# Temp_board_v4_0.net
KiCad netlist of a schematic drawn in EAGLE
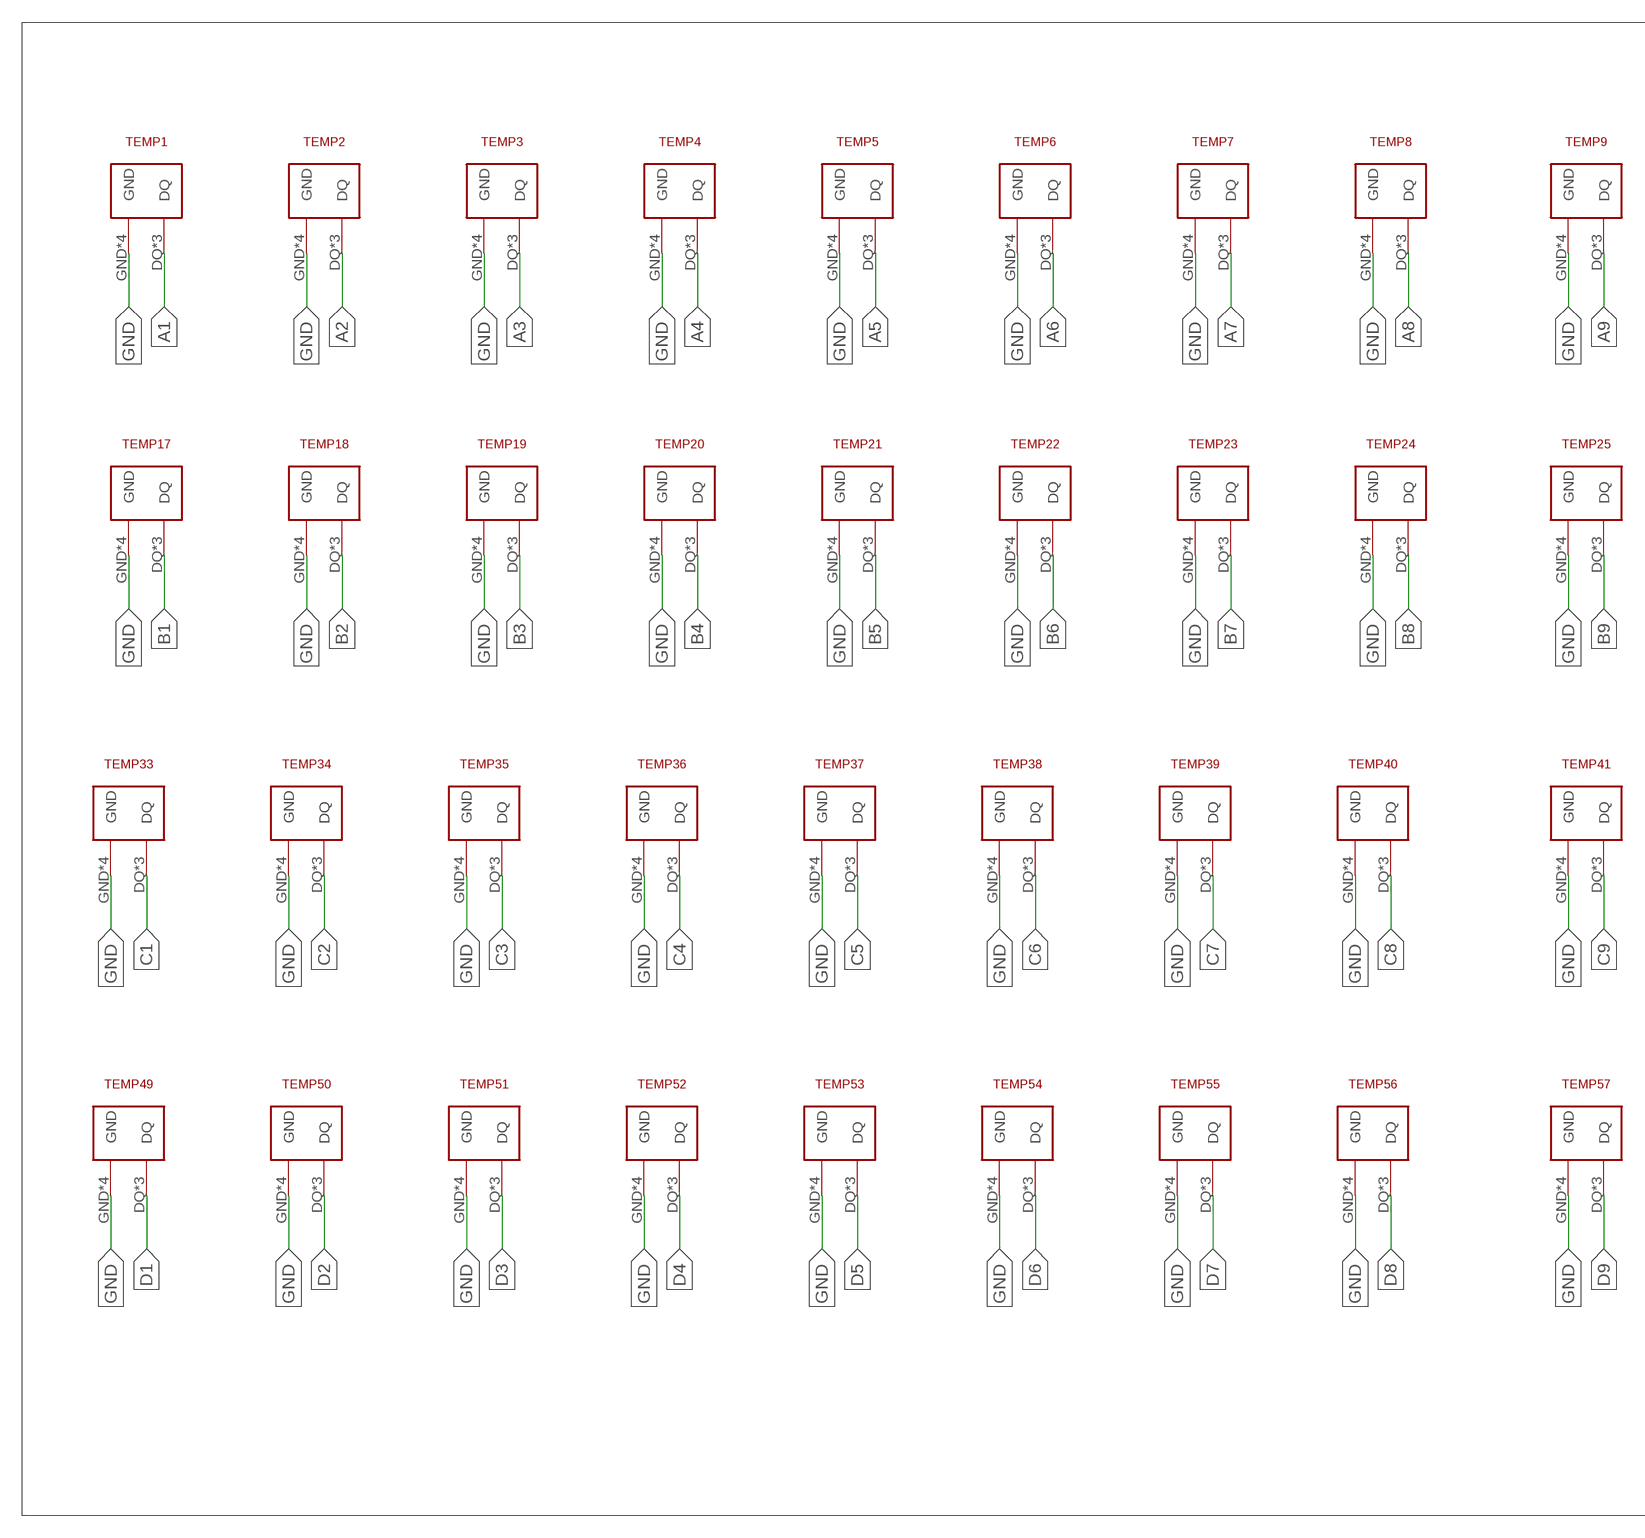
[diagram p0: schematic, sheet 1, part 1 of 2]
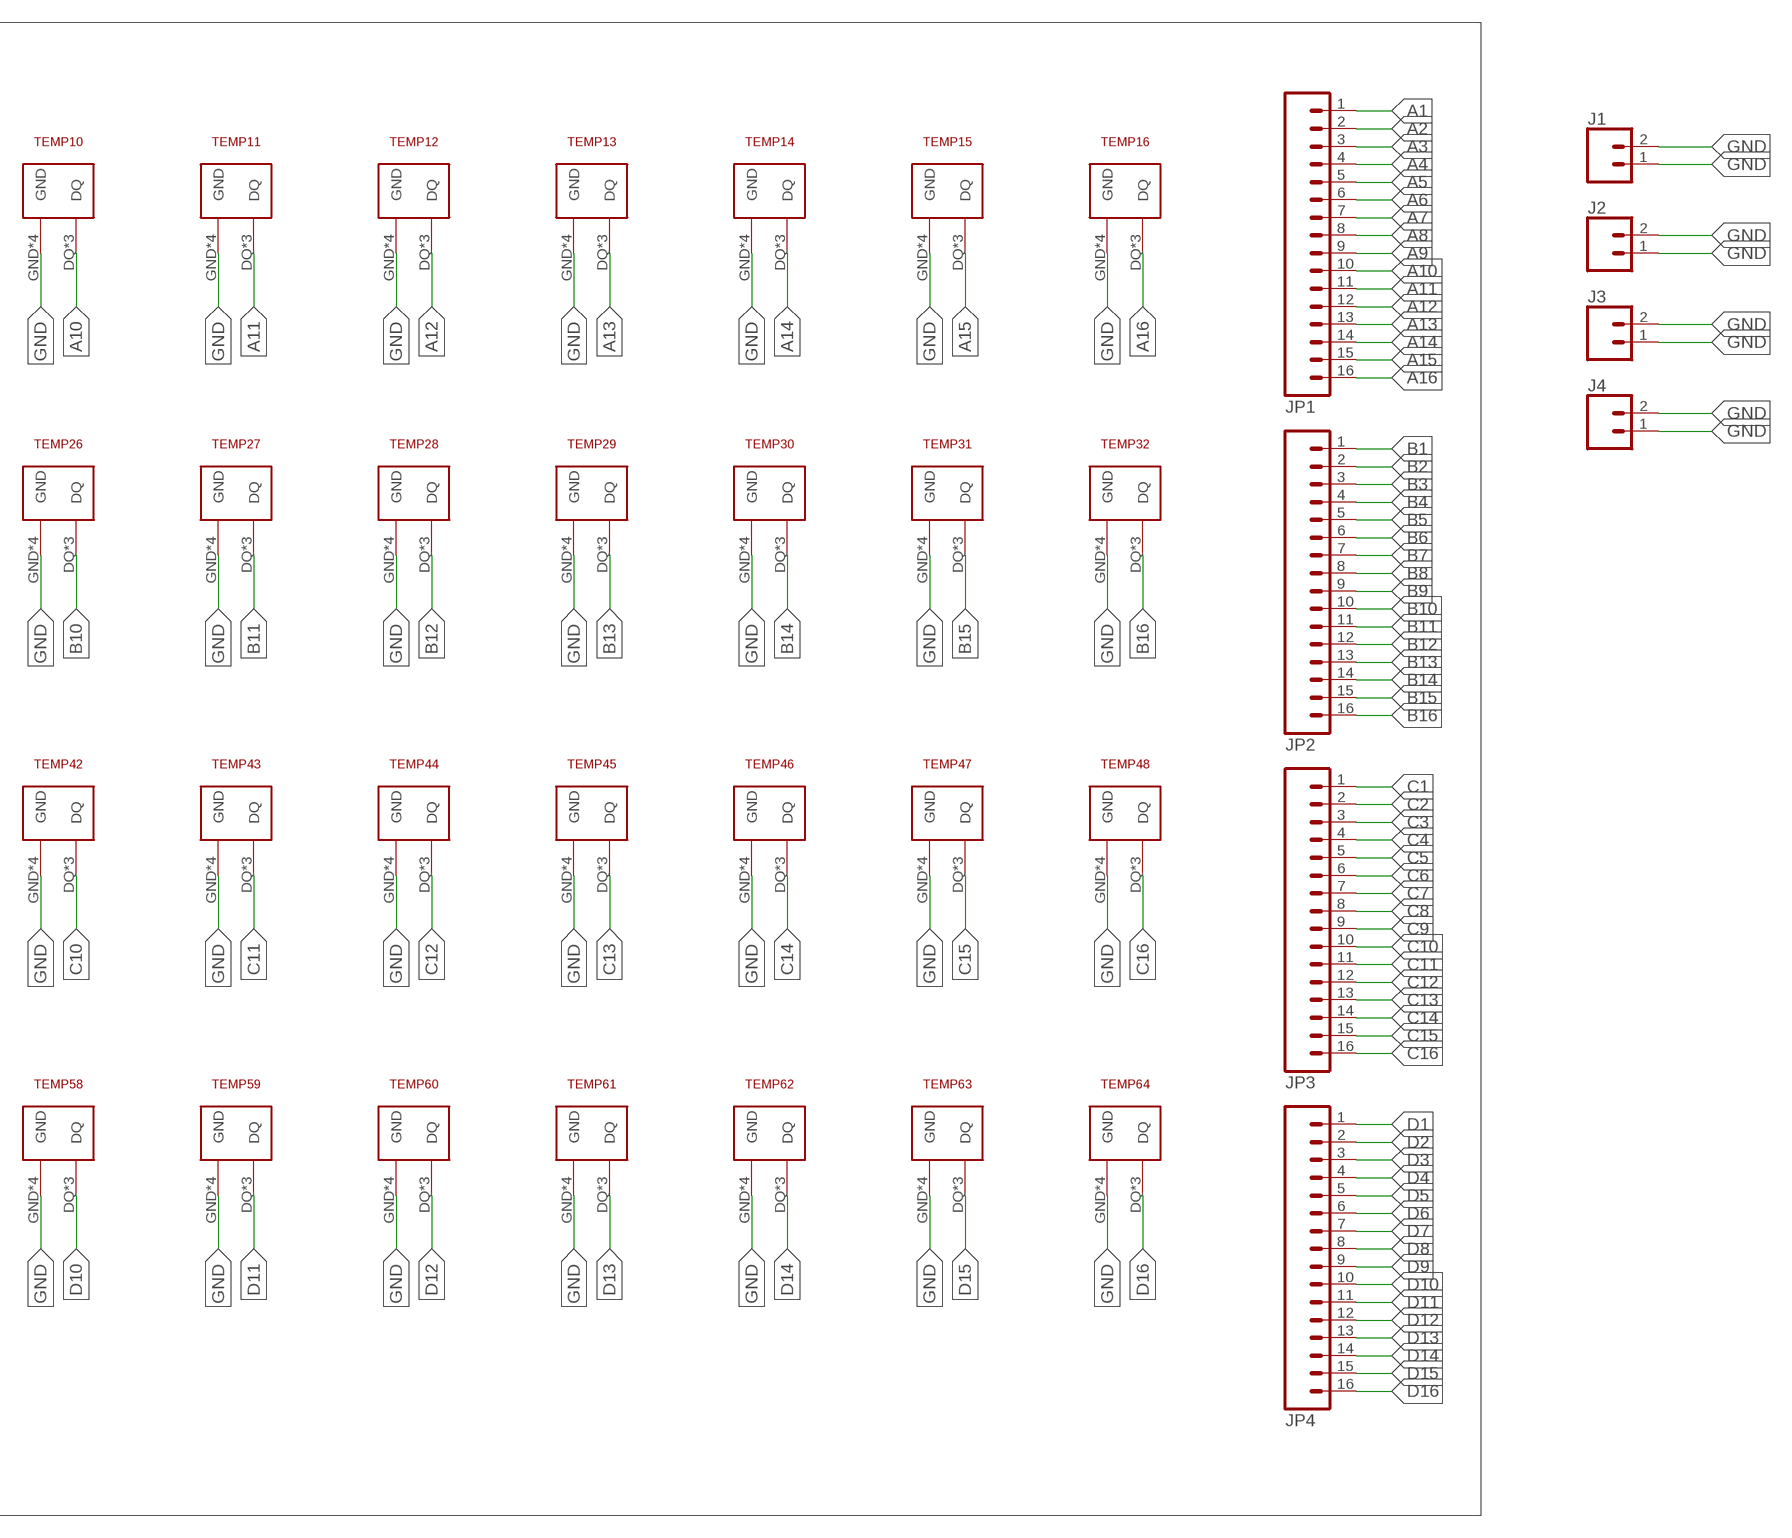
[diagram p1: schematic, sheet 1, part 2 of 2]

(export (version "E")
  (design (tool "Eeschema 10.0.6"))
  (components
    (comp (ref "J1")
      (value "CONN_02")
      (footprint "eagle-import:1X02")
      (libsource (lib "eagle-import") (part "CONN_02"))
    )
    (comp (ref "J2")
      (value "CONN_02")
      (footprint "eagle-import:1X02")
      (libsource (lib "eagle-import") (part "CONN_02"))
    )
    (comp (ref "J3")
      (value "CONN_02")
      (footprint "eagle-import:1X02")
      (libsource (lib "eagle-import") (part "CONN_02"))
    )
    (comp (ref "J4")
      (value "CONN_02")
      (footprint "eagle-import:1X02")
      (libsource (lib "eagle-import") (part "CONN_02"))
    )
    (comp (ref "JP1")
      (value "M16PTH")
      (footprint "eagle-import:1X16")
      (libsource (lib "eagle-import") (part "M16PTH"))
    )
    (comp (ref "JP2")
      (value "M16PTH")
      (footprint "eagle-import:1X16")
      (libsource (lib "eagle-import") (part "M16PTH"))
    )
    (comp (ref "JP3")
      (value "M16PTH")
      (footprint "eagle-import:1X16")
      (libsource (lib "eagle-import") (part "M16PTH"))
    )
    (comp (ref "JP4")
      (value "M16PTH")
      (footprint "eagle-import:1X16")
      (libsource (lib "eagle-import") (part "M16PTH"))
    )
    (comp (ref "TEMP1")
      (value "TEMP_TEST_ALL")
      (footprint "eagle-import:TEMP_TEST_PACKAGE")
      (libsource (lib "eagle-import") (part "TEMP_TEST_ALL"))
    )
    (comp (ref "TEMP2")
      (value "TEMP_TEST_ALL")
      (footprint "eagle-import:TEMP_TEST_PACKAGE")
      (libsource (lib "eagle-import") (part "TEMP_TEST_ALL"))
    )
    (comp (ref "TEMP3")
      (value "TEMP_TEST_ALL")
      (footprint "eagle-import:TEMP_TEST_PACKAGE")
      (libsource (lib "eagle-import") (part "TEMP_TEST_ALL"))
    )
    (comp (ref "TEMP4")
      (value "TEMP_TEST_ALL")
      (footprint "eagle-import:TEMP_TEST_PACKAGE")
      (libsource (lib "eagle-import") (part "TEMP_TEST_ALL"))
    )
    (comp (ref "TEMP5")
      (value "TEMP_TEST_ALL")
      (footprint "eagle-import:TEMP_TEST_PACKAGE")
      (libsource (lib "eagle-import") (part "TEMP_TEST_ALL"))
    )
    (comp (ref "TEMP6")
      (value "TEMP_TEST_ALL")
      (footprint "eagle-import:TEMP_TEST_PACKAGE")
      (libsource (lib "eagle-import") (part "TEMP_TEST_ALL"))
    )
    (comp (ref "TEMP7")
      (value "TEMP_TEST_ALL")
      (footprint "eagle-import:TEMP_TEST_PACKAGE")
      (libsource (lib "eagle-import") (part "TEMP_TEST_ALL"))
    )
    (comp (ref "TEMP8")
      (value "TEMP_TEST_ALL")
      (footprint "eagle-import:TEMP_TEST_PACKAGE")
      (libsource (lib "eagle-import") (part "TEMP_TEST_ALL"))
    )
    (comp (ref "TEMP9")
      (value "TEMP_TEST_ALL")
      (footprint "eagle-import:TEMP_TEST_PACKAGE")
      (libsource (lib "eagle-import") (part "TEMP_TEST_ALL"))
    )
    (comp (ref "TEMP10")
      (value "TEMP_TEST_ALL")
      (footprint "eagle-import:TEMP_TEST_PACKAGE")
      (libsource (lib "eagle-import") (part "TEMP_TEST_ALL"))
    )
    (comp (ref "TEMP11")
      (value "TEMP_TEST_ALL")
      (footprint "eagle-import:TEMP_TEST_PACKAGE")
      (libsource (lib "eagle-import") (part "TEMP_TEST_ALL"))
    )
    (comp (ref "TEMP12")
      (value "TEMP_TEST_ALL")
      (footprint "eagle-import:TEMP_TEST_PACKAGE")
      (libsource (lib "eagle-import") (part "TEMP_TEST_ALL"))
    )
    (comp (ref "TEMP13")
      (value "TEMP_TEST_ALL")
      (footprint "eagle-import:TEMP_TEST_PACKAGE")
      (libsource (lib "eagle-import") (part "TEMP_TEST_ALL"))
    )
    (comp (ref "TEMP14")
      (value "TEMP_TEST_ALL")
      (footprint "eagle-import:TEMP_TEST_PACKAGE")
      (libsource (lib "eagle-import") (part "TEMP_TEST_ALL"))
    )
    (comp (ref "TEMP15")
      (value "TEMP_TEST_ALL")
      (footprint "eagle-import:TEMP_TEST_PACKAGE")
      (libsource (lib "eagle-import") (part "TEMP_TEST_ALL"))
    )
    (comp (ref "TEMP16")
      (value "TEMP_TEST_ALL")
      (footprint "eagle-import:TEMP_TEST_PACKAGE")
      (libsource (lib "eagle-import") (part "TEMP_TEST_ALL"))
    )
    (comp (ref "TEMP17")
      (value "TEMP_TEST_ALL")
      (footprint "eagle-import:TEMP_TEST_PACKAGE")
      (libsource (lib "eagle-import") (part "TEMP_TEST_ALL"))
    )
    (comp (ref "TEMP18")
      (value "TEMP_TEST_ALL")
      (footprint "eagle-import:TEMP_TEST_PACKAGE")
      (libsource (lib "eagle-import") (part "TEMP_TEST_ALL"))
    )
    (comp (ref "TEMP19")
      (value "TEMP_TEST_ALL")
      (footprint "eagle-import:TEMP_TEST_PACKAGE")
      (libsource (lib "eagle-import") (part "TEMP_TEST_ALL"))
    )
    (comp (ref "TEMP20")
      (value "TEMP_TEST_ALL")
      (footprint "eagle-import:TEMP_TEST_PACKAGE")
      (libsource (lib "eagle-import") (part "TEMP_TEST_ALL"))
    )
    (comp (ref "TEMP21")
      (value "TEMP_TEST_ALL")
      (footprint "eagle-import:TEMP_TEST_PACKAGE")
      (libsource (lib "eagle-import") (part "TEMP_TEST_ALL"))
    )
    (comp (ref "TEMP22")
      (value "TEMP_TEST_ALL")
      (footprint "eagle-import:TEMP_TEST_PACKAGE")
      (libsource (lib "eagle-import") (part "TEMP_TEST_ALL"))
    )
    (comp (ref "TEMP23")
      (value "TEMP_TEST_ALL")
      (footprint "eagle-import:TEMP_TEST_PACKAGE")
      (libsource (lib "eagle-import") (part "TEMP_TEST_ALL"))
    )
    (comp (ref "TEMP24")
      (value "TEMP_TEST_ALL")
      (footprint "eagle-import:TEMP_TEST_PACKAGE")
      (libsource (lib "eagle-import") (part "TEMP_TEST_ALL"))
    )
    (comp (ref "TEMP25")
      (value "TEMP_TEST_ALL")
      (footprint "eagle-import:TEMP_TEST_PACKAGE")
      (libsource (lib "eagle-import") (part "TEMP_TEST_ALL"))
    )
    (comp (ref "TEMP26")
      (value "TEMP_TEST_ALL")
      (footprint "eagle-import:TEMP_TEST_PACKAGE")
      (libsource (lib "eagle-import") (part "TEMP_TEST_ALL"))
    )
    (comp (ref "TEMP27")
      (value "TEMP_TEST_ALL")
      (footprint "eagle-import:TEMP_TEST_PACKAGE")
      (libsource (lib "eagle-import") (part "TEMP_TEST_ALL"))
    )
    (comp (ref "TEMP28")
      (value "TEMP_TEST_ALL")
      (footprint "eagle-import:TEMP_TEST_PACKAGE")
      (libsource (lib "eagle-import") (part "TEMP_TEST_ALL"))
    )
    (comp (ref "TEMP29")
      (value "TEMP_TEST_ALL")
      (footprint "eagle-import:TEMP_TEST_PACKAGE")
      (libsource (lib "eagle-import") (part "TEMP_TEST_ALL"))
    )
    (comp (ref "TEMP30")
      (value "TEMP_TEST_ALL")
      (footprint "eagle-import:TEMP_TEST_PACKAGE")
      (libsource (lib "eagle-import") (part "TEMP_TEST_ALL"))
    )
    (comp (ref "TEMP31")
      (value "TEMP_TEST_ALL")
      (footprint "eagle-import:TEMP_TEST_PACKAGE")
      (libsource (lib "eagle-import") (part "TEMP_TEST_ALL"))
    )
    (comp (ref "TEMP32")
      (value "TEMP_TEST_ALL")
      (footprint "eagle-import:TEMP_TEST_PACKAGE")
      (libsource (lib "eagle-import") (part "TEMP_TEST_ALL"))
    )
    (comp (ref "TEMP33")
      (value "TEMP_TEST_ALL")
      (footprint "eagle-import:TEMP_TEST_PACKAGE")
      (libsource (lib "eagle-import") (part "TEMP_TEST_ALL"))
    )
    (comp (ref "TEMP34")
      (value "TEMP_TEST_ALL")
      (footprint "eagle-import:TEMP_TEST_PACKAGE")
      (libsource (lib "eagle-import") (part "TEMP_TEST_ALL"))
    )
    (comp (ref "TEMP35")
      (value "TEMP_TEST_ALL")
      (footprint "eagle-import:TEMP_TEST_PACKAGE")
      (libsource (lib "eagle-import") (part "TEMP_TEST_ALL"))
    )
    (comp (ref "TEMP36")
      (value "TEMP_TEST_ALL")
      (footprint "eagle-import:TEMP_TEST_PACKAGE")
      (libsource (lib "eagle-import") (part "TEMP_TEST_ALL"))
    )
    (comp (ref "TEMP37")
      (value "TEMP_TEST_ALL")
      (footprint "eagle-import:TEMP_TEST_PACKAGE")
      (libsource (lib "eagle-import") (part "TEMP_TEST_ALL"))
    )
    (comp (ref "TEMP38")
      (value "TEMP_TEST_ALL")
      (footprint "eagle-import:TEMP_TEST_PACKAGE")
      (libsource (lib "eagle-import") (part "TEMP_TEST_ALL"))
    )
    (comp (ref "TEMP39")
      (value "TEMP_TEST_ALL")
      (footprint "eagle-import:TEMP_TEST_PACKAGE")
      (libsource (lib "eagle-import") (part "TEMP_TEST_ALL"))
    )
    (comp (ref "TEMP40")
      (value "TEMP_TEST_ALL")
      (footprint "eagle-import:TEMP_TEST_PACKAGE")
      (libsource (lib "eagle-import") (part "TEMP_TEST_ALL"))
    )
    (comp (ref "TEMP41")
      (value "TEMP_TEST_ALL")
      (footprint "eagle-import:TEMP_TEST_PACKAGE")
      (libsource (lib "eagle-import") (part "TEMP_TEST_ALL"))
    )
    (comp (ref "TEMP42")
      (value "TEMP_TEST_ALL")
      (footprint "eagle-import:TEMP_TEST_PACKAGE")
      (libsource (lib "eagle-import") (part "TEMP_TEST_ALL"))
    )
    (comp (ref "TEMP43")
      (value "TEMP_TEST_ALL")
      (footprint "eagle-import:TEMP_TEST_PACKAGE")
      (libsource (lib "eagle-import") (part "TEMP_TEST_ALL"))
    )
    (comp (ref "TEMP44")
      (value "TEMP_TEST_ALL")
      (footprint "eagle-import:TEMP_TEST_PACKAGE")
      (libsource (lib "eagle-import") (part "TEMP_TEST_ALL"))
    )
    (comp (ref "TEMP45")
      (value "TEMP_TEST_ALL")
      (footprint "eagle-import:TEMP_TEST_PACKAGE")
      (libsource (lib "eagle-import") (part "TEMP_TEST_ALL"))
    )
    (comp (ref "TEMP46")
      (value "TEMP_TEST_ALL")
      (footprint "eagle-import:TEMP_TEST_PACKAGE")
      (libsource (lib "eagle-import") (part "TEMP_TEST_ALL"))
    )
    (comp (ref "TEMP47")
      (value "TEMP_TEST_ALL")
      (footprint "eagle-import:TEMP_TEST_PACKAGE")
      (libsource (lib "eagle-import") (part "TEMP_TEST_ALL"))
    )
    (comp (ref "TEMP48")
      (value "TEMP_TEST_ALL")
      (footprint "eagle-import:TEMP_TEST_PACKAGE")
      (libsource (lib "eagle-import") (part "TEMP_TEST_ALL"))
    )
    (comp (ref "TEMP49")
      (value "TEMP_TEST_ALL")
      (footprint "eagle-import:TEMP_TEST_PACKAGE")
      (libsource (lib "eagle-import") (part "TEMP_TEST_ALL"))
    )
    (comp (ref "TEMP50")
      (value "TEMP_TEST_ALL")
      (footprint "eagle-import:TEMP_TEST_PACKAGE")
      (libsource (lib "eagle-import") (part "TEMP_TEST_ALL"))
    )
    (comp (ref "TEMP51")
      (value "TEMP_TEST_ALL")
      (footprint "eagle-import:TEMP_TEST_PACKAGE")
      (libsource (lib "eagle-import") (part "TEMP_TEST_ALL"))
    )
    (comp (ref "TEMP52")
      (value "TEMP_TEST_ALL")
      (footprint "eagle-import:TEMP_TEST_PACKAGE")
      (libsource (lib "eagle-import") (part "TEMP_TEST_ALL"))
    )
    (comp (ref "TEMP53")
      (value "TEMP_TEST_ALL")
      (footprint "eagle-import:TEMP_TEST_PACKAGE")
      (libsource (lib "eagle-import") (part "TEMP_TEST_ALL"))
    )
    (comp (ref "TEMP54")
      (value "TEMP_TEST_ALL")
      (footprint "eagle-import:TEMP_TEST_PACKAGE")
      (libsource (lib "eagle-import") (part "TEMP_TEST_ALL"))
    )
    (comp (ref "TEMP55")
      (value "TEMP_TEST_ALL")
      (footprint "eagle-import:TEMP_TEST_PACKAGE")
      (libsource (lib "eagle-import") (part "TEMP_TEST_ALL"))
    )
    (comp (ref "TEMP56")
      (value "TEMP_TEST_ALL")
      (footprint "eagle-import:TEMP_TEST_PACKAGE")
      (libsource (lib "eagle-import") (part "TEMP_TEST_ALL"))
    )
    (comp (ref "TEMP57")
      (value "TEMP_TEST_ALL")
      (footprint "eagle-import:TEMP_TEST_PACKAGE")
      (libsource (lib "eagle-import") (part "TEMP_TEST_ALL"))
    )
    (comp (ref "TEMP58")
      (value "TEMP_TEST_ALL")
      (footprint "eagle-import:TEMP_TEST_PACKAGE")
      (libsource (lib "eagle-import") (part "TEMP_TEST_ALL"))
    )
    (comp (ref "TEMP59")
      (value "TEMP_TEST_ALL")
      (footprint "eagle-import:TEMP_TEST_PACKAGE")
      (libsource (lib "eagle-import") (part "TEMP_TEST_ALL"))
    )
    (comp (ref "TEMP60")
      (value "TEMP_TEST_ALL")
      (footprint "eagle-import:TEMP_TEST_PACKAGE")
      (libsource (lib "eagle-import") (part "TEMP_TEST_ALL"))
    )
    (comp (ref "TEMP61")
      (value "TEMP_TEST_ALL")
      (footprint "eagle-import:TEMP_TEST_PACKAGE")
      (libsource (lib "eagle-import") (part "TEMP_TEST_ALL"))
    )
    (comp (ref "TEMP62")
      (value "TEMP_TEST_ALL")
      (footprint "eagle-import:TEMP_TEST_PACKAGE")
      (libsource (lib "eagle-import") (part "TEMP_TEST_ALL"))
    )
    (comp (ref "TEMP63")
      (value "TEMP_TEST_ALL")
      (footprint "eagle-import:TEMP_TEST_PACKAGE")
      (libsource (lib "eagle-import") (part "TEMP_TEST_ALL"))
    )
    (comp (ref "TEMP64")
      (value "TEMP_TEST_ALL")
      (footprint "eagle-import:TEMP_TEST_PACKAGE")
      (libsource (lib "eagle-import") (part "TEMP_TEST_ALL"))
    )
  )
  (nets
    (net (code "1") (name "A1") (class "Default")
      (node (ref "JP1") (pin "1") (pinfunction "1_1") (pintype "passive"))
      (node (ref "TEMP1") (pin "DQ") (pinfunction "DQ_DQ") (pintype "bidirectional"))
      (node (ref "TEMP1") (pin "DQ1") (pinfunction "DQ_DQ1") (pintype "bidirectional"))
      (node (ref "TEMP1") (pin "DQ2") (pinfunction "DQ_DQ2") (pintype "bidirectional"))
    )
    (net (code "2") (name "A2") (class "Default")
      (node (ref "JP1") (pin "2") (pinfunction "2_2") (pintype "passive"))
      (node (ref "TEMP2") (pin "DQ") (pinfunction "DQ_DQ") (pintype "bidirectional"))
      (node (ref "TEMP2") (pin "DQ1") (pinfunction "DQ_DQ1") (pintype "bidirectional"))
      (node (ref "TEMP2") (pin "DQ2") (pinfunction "DQ_DQ2") (pintype "bidirectional"))
    )
    (net (code "3") (name "A3") (class "Default")
      (node (ref "JP1") (pin "3") (pinfunction "3_3") (pintype "passive"))
      (node (ref "TEMP3") (pin "DQ") (pinfunction "DQ_DQ") (pintype "bidirectional"))
      (node (ref "TEMP3") (pin "DQ1") (pinfunction "DQ_DQ1") (pintype "bidirectional"))
      (node (ref "TEMP3") (pin "DQ2") (pinfunction "DQ_DQ2") (pintype "bidirectional"))
    )
    (net (code "4") (name "A4") (class "Default")
      (node (ref "JP1") (pin "4") (pinfunction "4_4") (pintype "passive"))
      (node (ref "TEMP4") (pin "DQ") (pinfunction "DQ_DQ") (pintype "bidirectional"))
      (node (ref "TEMP4") (pin "DQ1") (pinfunction "DQ_DQ1") (pintype "bidirectional"))
      (node (ref "TEMP4") (pin "DQ2") (pinfunction "DQ_DQ2") (pintype "bidirectional"))
    )
    (net (code "5") (name "A5") (class "Default")
      (node (ref "JP1") (pin "5") (pinfunction "5_5") (pintype "passive"))
      (node (ref "TEMP5") (pin "DQ") (pinfunction "DQ_DQ") (pintype "bidirectional"))
      (node (ref "TEMP5") (pin "DQ1") (pinfunction "DQ_DQ1") (pintype "bidirectional"))
      (node (ref "TEMP5") (pin "DQ2") (pinfunction "DQ_DQ2") (pintype "bidirectional"))
    )
    (net (code "6") (name "A6") (class "Default")
      (node (ref "JP1") (pin "6") (pinfunction "6_6") (pintype "passive"))
      (node (ref "TEMP6") (pin "DQ") (pinfunction "DQ_DQ") (pintype "bidirectional"))
      (node (ref "TEMP6") (pin "DQ1") (pinfunction "DQ_DQ1") (pintype "bidirectional"))
      (node (ref "TEMP6") (pin "DQ2") (pinfunction "DQ_DQ2") (pintype "bidirectional"))
    )
    (net (code "7") (name "A7") (class "Default")
      (node (ref "JP1") (pin "7") (pinfunction "7_7") (pintype "passive"))
      (node (ref "TEMP7") (pin "DQ") (pinfunction "DQ_DQ") (pintype "bidirectional"))
      (node (ref "TEMP7") (pin "DQ1") (pinfunction "DQ_DQ1") (pintype "bidirectional"))
      (node (ref "TEMP7") (pin "DQ2") (pinfunction "DQ_DQ2") (pintype "bidirectional"))
    )
    (net (code "8") (name "A8") (class "Default")
      (node (ref "JP1") (pin "8") (pinfunction "8_8") (pintype "passive"))
      (node (ref "TEMP8") (pin "DQ") (pinfunction "DQ_DQ") (pintype "bidirectional"))
      (node (ref "TEMP8") (pin "DQ1") (pinfunction "DQ_DQ1") (pintype "bidirectional"))
      (node (ref "TEMP8") (pin "DQ2") (pinfunction "DQ_DQ2") (pintype "bidirectional"))
    )
    (net (code "9") (name "A9") (class "Default")
      (node (ref "JP1") (pin "9") (pinfunction "9_9") (pintype "passive"))
      (node (ref "TEMP9") (pin "DQ") (pinfunction "DQ_DQ") (pintype "bidirectional"))
      (node (ref "TEMP9") (pin "DQ1") (pinfunction "DQ_DQ1") (pintype "bidirectional"))
      (node (ref "TEMP9") (pin "DQ2") (pinfunction "DQ_DQ2") (pintype "bidirectional"))
    )
    (net (code "10") (name "A10") (class "Default")
      (node (ref "JP1") (pin "10") (pinfunction "10_10") (pintype "passive"))
      (node (ref "TEMP10") (pin "DQ") (pinfunction "DQ_DQ") (pintype "bidirectional"))
      (node (ref "TEMP10") (pin "DQ1") (pinfunction "DQ_DQ1") (pintype "bidirectional"))
      (node (ref "TEMP10") (pin "DQ2") (pinfunction "DQ_DQ2") (pintype "bidirectional"))
    )
    (net (code "11") (name "A11") (class "Default")
      (node (ref "JP1") (pin "11") (pinfunction "11_11") (pintype "passive"))
      (node (ref "TEMP11") (pin "DQ") (pinfunction "DQ_DQ") (pintype "bidirectional"))
      (node (ref "TEMP11") (pin "DQ1") (pinfunction "DQ_DQ1") (pintype "bidirectional"))
      (node (ref "TEMP11") (pin "DQ2") (pinfunction "DQ_DQ2") (pintype "bidirectional"))
    )
    (net (code "12") (name "A12") (class "Default")
      (node (ref "JP1") (pin "12") (pinfunction "12_12") (pintype "passive"))
      (node (ref "TEMP12") (pin "DQ") (pinfunction "DQ_DQ") (pintype "bidirectional"))
      (node (ref "TEMP12") (pin "DQ1") (pinfunction "DQ_DQ1") (pintype "bidirectional"))
      (node (ref "TEMP12") (pin "DQ2") (pinfunction "DQ_DQ2") (pintype "bidirectional"))
    )
    (net (code "13") (name "A13") (class "Default")
      (node (ref "JP1") (pin "13") (pinfunction "13_13") (pintype "passive"))
      (node (ref "TEMP13") (pin "DQ") (pinfunction "DQ_DQ") (pintype "bidirectional"))
      (node (ref "TEMP13") (pin "DQ1") (pinfunction "DQ_DQ1") (pintype "bidirectional"))
      (node (ref "TEMP13") (pin "DQ2") (pinfunction "DQ_DQ2") (pintype "bidirectional"))
    )
    (net (code "14") (name "A14") (class "Default")
      (node (ref "JP1") (pin "14") (pinfunction "14_14") (pintype "passive"))
      (node (ref "TEMP14") (pin "DQ") (pinfunction "DQ_DQ") (pintype "bidirectional"))
      (node (ref "TEMP14") (pin "DQ1") (pinfunction "DQ_DQ1") (pintype "bidirectional"))
      (node (ref "TEMP14") (pin "DQ2") (pinfunction "DQ_DQ2") (pintype "bidirectional"))
    )
    (net (code "15") (name "A15") (class "Default")
      (node (ref "JP1") (pin "15") (pinfunction "15_15") (pintype "passive"))
      (node (ref "TEMP15") (pin "DQ") (pinfunction "DQ_DQ") (pintype "bidirectional"))
      (node (ref "TEMP15") (pin "DQ1") (pinfunction "DQ_DQ1") (pintype "bidirectional"))
      (node (ref "TEMP15") (pin "DQ2") (pinfunction "DQ_DQ2") (pintype "bidirectional"))
    )
    (net (code "16") (name "A16") (class "Default")
      (node (ref "JP1") (pin "16") (pinfunction "16_16") (pintype "passive"))
      (node (ref "TEMP16") (pin "DQ") (pinfunction "DQ_DQ") (pintype "bidirectional"))
      (node (ref "TEMP16") (pin "DQ1") (pinfunction "DQ_DQ1") (pintype "bidirectional"))
      (node (ref "TEMP16") (pin "DQ2") (pinfunction "DQ_DQ2") (pintype "bidirectional"))
    )
    (net (code "17") (name "B1") (class "Default")
      (node (ref "JP2") (pin "1") (pinfunction "1_1") (pintype "passive"))
      (node (ref "TEMP17") (pin "DQ") (pinfunction "DQ_DQ") (pintype "bidirectional"))
      (node (ref "TEMP17") (pin "DQ1") (pinfunction "DQ_DQ1") (pintype "bidirectional"))
      (node (ref "TEMP17") (pin "DQ2") (pinfunction "DQ_DQ2") (pintype "bidirectional"))
    )
    (net (code "18") (name "B2") (class "Default")
      (node (ref "JP2") (pin "2") (pinfunction "2_2") (pintype "passive"))
      (node (ref "TEMP18") (pin "DQ") (pinfunction "DQ_DQ") (pintype "bidirectional"))
      (node (ref "TEMP18") (pin "DQ1") (pinfunction "DQ_DQ1") (pintype "bidirectional"))
      (node (ref "TEMP18") (pin "DQ2") (pinfunction "DQ_DQ2") (pintype "bidirectional"))
    )
    (net (code "19") (name "B3") (class "Default")
      (node (ref "JP2") (pin "3") (pinfunction "3_3") (pintype "passive"))
      (node (ref "TEMP19") (pin "DQ") (pinfunction "DQ_DQ") (pintype "bidirectional"))
      (node (ref "TEMP19") (pin "DQ1") (pinfunction "DQ_DQ1") (pintype "bidirectional"))
      (node (ref "TEMP19") (pin "DQ2") (pinfunction "DQ_DQ2") (pintype "bidirectional"))
    )
    (net (code "20") (name "B4") (class "Default")
      (node (ref "JP2") (pin "4") (pinfunction "4_4") (pintype "passive"))
      (node (ref "TEMP20") (pin "DQ") (pinfunction "DQ_DQ") (pintype "bidirectional"))
      (node (ref "TEMP20") (pin "DQ1") (pinfunction "DQ_DQ1") (pintype "bidirectional"))
      (node (ref "TEMP20") (pin "DQ2") (pinfunction "DQ_DQ2") (pintype "bidirectional"))
    )
    (net (code "21") (name "B5") (class "Default")
      (node (ref "JP2") (pin "5") (pinfunction "5_5") (pintype "passive"))
      (node (ref "TEMP21") (pin "DQ") (pinfunction "DQ_DQ") (pintype "bidirectional"))
      (node (ref "TEMP21") (pin "DQ1") (pinfunction "DQ_DQ1") (pintype "bidirectional"))
      (node (ref "TEMP21") (pin "DQ2") (pinfunction "DQ_DQ2") (pintype "bidirectional"))
    )
    (net (code "22") (name "B6") (class "Default")
      (node (ref "JP2") (pin "6") (pinfunction "6_6") (pintype "passive"))
      (node (ref "TEMP22") (pin "DQ") (pinfunction "DQ_DQ") (pintype "bidirectional"))
      (node (ref "TEMP22") (pin "DQ1") (pinfunction "DQ_DQ1") (pintype "bidirectional"))
      (node (ref "TEMP22") (pin "DQ2") (pinfunction "DQ_DQ2") (pintype "bidirectional"))
    )
    (net (code "23") (name "B7") (class "Default")
      (node (ref "JP2") (pin "7") (pinfunction "7_7") (pintype "passive"))
      (node (ref "TEMP23") (pin "DQ") (pinfunction "DQ_DQ") (pintype "bidirectional"))
      (node (ref "TEMP23") (pin "DQ1") (pinfunction "DQ_DQ1") (pintype "bidirectional"))
      (node (ref "TEMP23") (pin "DQ2") (pinfunction "DQ_DQ2") (pintype "bidirectional"))
    )
    (net (code "24") (name "B8") (class "Default")
      (node (ref "JP2") (pin "8") (pinfunction "8_8") (pintype "passive"))
      (node (ref "TEMP24") (pin "DQ") (pinfunction "DQ_DQ") (pintype "bidirectional"))
      (node (ref "TEMP24") (pin "DQ1") (pinfunction "DQ_DQ1") (pintype "bidirectional"))
      (node (ref "TEMP24") (pin "DQ2") (pinfunction "DQ_DQ2") (pintype "bidirectional"))
    )
    (net (code "25") (name "B9") (class "Default")
      (node (ref "JP2") (pin "9") (pinfunction "9_9") (pintype "passive"))
      (node (ref "TEMP25") (pin "DQ") (pinfunction "DQ_DQ") (pintype "bidirectional"))
      (node (ref "TEMP25") (pin "DQ1") (pinfunction "DQ_DQ1") (pintype "bidirectional"))
      (node (ref "TEMP25") (pin "DQ2") (pinfunction "DQ_DQ2") (pintype "bidirectional"))
    )
    (net (code "26") (name "B10") (class "Default")
      (node (ref "JP2") (pin "10") (pinfunction "10_10") (pintype "passive"))
      (node (ref "TEMP26") (pin "DQ") (pinfunction "DQ_DQ") (pintype "bidirectional"))
      (node (ref "TEMP26") (pin "DQ1") (pinfunction "DQ_DQ1") (pintype "bidirectional"))
      (node (ref "TEMP26") (pin "DQ2") (pinfunction "DQ_DQ2") (pintype "bidirectional"))
    )
    (net (code "27") (name "B11") (class "Default")
      (node (ref "JP2") (pin "11") (pinfunction "11_11") (pintype "passive"))
      (node (ref "TEMP27") (pin "DQ") (pinfunction "DQ_DQ") (pintype "bidirectional"))
      (node (ref "TEMP27") (pin "DQ1") (pinfunction "DQ_DQ1") (pintype "bidirectional"))
      (node (ref "TEMP27") (pin "DQ2") (pinfunction "DQ_DQ2") (pintype "bidirectional"))
    )
    (net (code "28") (name "B12") (class "Default")
      (node (ref "JP2") (pin "12") (pinfunction "12_12") (pintype "passive"))
      (node (ref "TEMP28") (pin "DQ") (pinfunction "DQ_DQ") (pintype "bidirectional"))
      (node (ref "TEMP28") (pin "DQ1") (pinfunction "DQ_DQ1") (pintype "bidirectional"))
      (node (ref "TEMP28") (pin "DQ2") (pinfunction "DQ_DQ2") (pintype "bidirectional"))
    )
    (net (code "29") (name "B13") (class "Default")
      (node (ref "JP2") (pin "13") (pinfunction "13_13") (pintype "passive"))
      (node (ref "TEMP29") (pin "DQ") (pinfunction "DQ_DQ") (pintype "bidirectional"))
      (node (ref "TEMP29") (pin "DQ1") (pinfunction "DQ_DQ1") (pintype "bidirectional"))
      (node (ref "TEMP29") (pin "DQ2") (pinfunction "DQ_DQ2") (pintype "bidirectional"))
    )
    (net (code "30") (name "B14") (class "Default")
      (node (ref "JP2") (pin "14") (pinfunction "14_14") (pintype "passive"))
      (node (ref "TEMP30") (pin "DQ") (pinfunction "DQ_DQ") (pintype "bidirectional"))
      (node (ref "TEMP30") (pin "DQ1") (pinfunction "DQ_DQ1") (pintype "bidirectional"))
      (node (ref "TEMP30") (pin "DQ2") (pinfunction "DQ_DQ2") (pintype "bidirectional"))
    )
    (net (code "31") (name "B15") (class "Default")
      (node (ref "JP2") (pin "15") (pinfunction "15_15") (pintype "passive"))
      (node (ref "TEMP31") (pin "DQ") (pinfunction "DQ_DQ") (pintype "bidirectional"))
      (node (ref "TEMP31") (pin "DQ1") (pinfunction "DQ_DQ1") (pintype "bidirectional"))
      (node (ref "TEMP31") (pin "DQ2") (pinfunction "DQ_DQ2") (pintype "bidirectional"))
    )
    (net (code "32") (name "B16") (class "Default")
      (node (ref "JP2") (pin "16") (pinfunction "16_16") (pintype "passive"))
      (node (ref "TEMP32") (pin "DQ") (pinfunction "DQ_DQ") (pintype "bidirectional"))
      (node (ref "TEMP32") (pin "DQ1") (pinfunction "DQ_DQ1") (pintype "bidirectional"))
      (node (ref "TEMP32") (pin "DQ2") (pinfunction "DQ_DQ2") (pintype "bidirectional"))
    )
    (net (code "33") (name "C1") (class "Default")
      (node (ref "JP3") (pin "1") (pinfunction "1_1") (pintype "passive"))
      (node (ref "TEMP33") (pin "DQ") (pinfunction "DQ_DQ") (pintype "bidirectional"))
      (node (ref "TEMP33") (pin "DQ1") (pinfunction "DQ_DQ1") (pintype "bidirectional"))
      (node (ref "TEMP33") (pin "DQ2") (pinfunction "DQ_DQ2") (pintype "bidirectional"))
    )
    (net (code "34") (name "C2") (class "Default")
      (node (ref "JP3") (pin "2") (pinfunction "2_2") (pintype "passive"))
      (node (ref "TEMP34") (pin "DQ") (pinfunction "DQ_DQ") (pintype "bidirectional"))
      (node (ref "TEMP34") (pin "DQ1") (pinfunction "DQ_DQ1") (pintype "bidirectional"))
      (node (ref "TEMP34") (pin "DQ2") (pinfunction "DQ_DQ2") (pintype "bidirectional"))
    )
    (net (code "35") (name "C3") (class "Default")
      (node (ref "JP3") (pin "3") (pinfunction "3_3") (pintype "passive"))
      (node (ref "TEMP35") (pin "DQ") (pinfunction "DQ_DQ") (pintype "bidirectional"))
      (node (ref "TEMP35") (pin "DQ1") (pinfunction "DQ_DQ1") (pintype "bidirectional"))
      (node (ref "TEMP35") (pin "DQ2") (pinfunction "DQ_DQ2") (pintype "bidirectional"))
    )
    (net (code "36") (name "C4") (class "Default")
      (node (ref "JP3") (pin "4") (pinfunction "4_4") (pintype "passive"))
      (node (ref "TEMP36") (pin "DQ") (pinfunction "DQ_DQ") (pintype "bidirectional"))
      (node (ref "TEMP36") (pin "DQ1") (pinfunction "DQ_DQ1") (pintype "bidirectional"))
      (node (ref "TEMP36") (pin "DQ2") (pinfunction "DQ_DQ2") (pintype "bidirectional"))
    )
    (net (code "37") (name "C5") (class "Default")
      (node (ref "JP3") (pin "5") (pinfunction "5_5") (pintype "passive"))
      (node (ref "TEMP37") (pin "DQ") (pinfunction "DQ_DQ") (pintype "bidirectional"))
      (node (ref "TEMP37") (pin "DQ1") (pinfunction "DQ_DQ1") (pintype "bidirectional"))
      (node (ref "TEMP37") (pin "DQ2") (pinfunction "DQ_DQ2") (pintype "bidirectional"))
    )
    (net (code "38") (name "C6") (class "Default")
      (node (ref "JP3") (pin "6") (pinfunction "6_6") (pintype "passive"))
      (node (ref "TEMP38") (pin "DQ") (pinfunction "DQ_DQ") (pintype "bidirectional"))
      (node (ref "TEMP38") (pin "DQ1") (pinfunction "DQ_DQ1") (pintype "bidirectional"))
      (node (ref "TEMP38") (pin "DQ2") (pinfunction "DQ_DQ2") (pintype "bidirectional"))
    )
    (net (code "39") (name "C7") (class "Default")
      (node (ref "JP3") (pin "7") (pinfunction "7_7") (pintype "passive"))
      (node (ref "TEMP39") (pin "DQ") (pinfunction "DQ_DQ") (pintype "bidirectional"))
      (node (ref "TEMP39") (pin "DQ1") (pinfunction "DQ_DQ1") (pintype "bidirectional"))
      (node (ref "TEMP39") (pin "DQ2") (pinfunction "DQ_DQ2") (pintype "bidirectional"))
    )
    (net (code "40") (name "C8") (class "Default")
      (node (ref "JP3") (pin "8") (pinfunction "8_8") (pintype "passive"))
      (node (ref "TEMP40") (pin "DQ") (pinfunction "DQ_DQ") (pintype "bidirectional"))
      (node (ref "TEMP40") (pin "DQ1") (pinfunction "DQ_DQ1") (pintype "bidirectional"))
      (node (ref "TEMP40") (pin "DQ2") (pinfunction "DQ_DQ2") (pintype "bidirectional"))
    )
    (net (code "41") (name "C9") (class "Default")
      (node (ref "JP3") (pin "9") (pinfunction "9_9") (pintype "passive"))
      (node (ref "TEMP41") (pin "DQ") (pinfunction "DQ_DQ") (pintype "bidirectional"))
      (node (ref "TEMP41") (pin "DQ1") (pinfunction "DQ_DQ1") (pintype "bidirectional"))
      (node (ref "TEMP41") (pin "DQ2") (pinfunction "DQ_DQ2") (pintype "bidirectional"))
    )
    (net (code "42") (name "C10") (class "Default")
      (node (ref "JP3") (pin "10") (pinfunction "10_10") (pintype "passive"))
      (node (ref "TEMP42") (pin "DQ") (pinfunction "DQ_DQ") (pintype "bidirectional"))
      (node (ref "TEMP42") (pin "DQ1") (pinfunction "DQ_DQ1") (pintype "bidirectional"))
      (node (ref "TEMP42") (pin "DQ2") (pinfunction "DQ_DQ2") (pintype "bidirectional"))
    )
    (net (code "43") (name "C11") (class "Default")
      (node (ref "JP3") (pin "11") (pinfunction "11_11") (pintype "passive"))
      (node (ref "TEMP43") (pin "DQ") (pinfunction "DQ_DQ") (pintype "bidirectional"))
      (node (ref "TEMP43") (pin "DQ1") (pinfunction "DQ_DQ1") (pintype "bidirectional"))
      (node (ref "TEMP43") (pin "DQ2") (pinfunction "DQ_DQ2") (pintype "bidirectional"))
    )
    (net (code "44") (name "C12") (class "Default")
      (node (ref "JP3") (pin "12") (pinfunction "12_12") (pintype "passive"))
      (node (ref "TEMP44") (pin "DQ") (pinfunction "DQ_DQ") (pintype "bidirectional"))
      (node (ref "TEMP44") (pin "DQ1") (pinfunction "DQ_DQ1") (pintype "bidirectional"))
      (node (ref "TEMP44") (pin "DQ2") (pinfunction "DQ_DQ2") (pintype "bidirectional"))
    )
    (net (code "45") (name "C13") (class "Default")
      (node (ref "JP3") (pin "13") (pinfunction "13_13") (pintype "passive"))
      (node (ref "TEMP45") (pin "DQ") (pinfunction "DQ_DQ") (pintype "bidirectional"))
      (node (ref "TEMP45") (pin "DQ1") (pinfunction "DQ_DQ1") (pintype "bidirectional"))
      (node (ref "TEMP45") (pin "DQ2") (pinfunction "DQ_DQ2") (pintype "bidirectional"))
    )
    (net (code "46") (name "C14") (class "Default")
      (node (ref "JP3") (pin "14") (pinfunction "14_14") (pintype "passive"))
      (node (ref "TEMP46") (pin "DQ") (pinfunction "DQ_DQ") (pintype "bidirectional"))
      (node (ref "TEMP46") (pin "DQ1") (pinfunction "DQ_DQ1") (pintype "bidirectional"))
      (node (ref "TEMP46") (pin "DQ2") (pinfunction "DQ_DQ2") (pintype "bidirectional"))
    )
    (net (code "47") (name "C15") (class "Default")
      (node (ref "JP3") (pin "15") (pinfunction "15_15") (pintype "passive"))
      (node (ref "TEMP47") (pin "DQ") (pinfunction "DQ_DQ") (pintype "bidirectional"))
      (node (ref "TEMP47") (pin "DQ1") (pinfunction "DQ_DQ1") (pintype "bidirectional"))
      (node (ref "TEMP47") (pin "DQ2") (pinfunction "DQ_DQ2") (pintype "bidirectional"))
    )
    (net (code "48") (name "C16") (class "Default")
      (node (ref "JP3") (pin "16") (pinfunction "16_16") (pintype "passive"))
      (node (ref "TEMP48") (pin "DQ") (pinfunction "DQ_DQ") (pintype "bidirectional"))
      (node (ref "TEMP48") (pin "DQ1") (pinfunction "DQ_DQ1") (pintype "bidirectional"))
      (node (ref "TEMP48") (pin "DQ2") (pinfunction "DQ_DQ2") (pintype "bidirectional"))
    )
    (net (code "49") (name "D1") (class "Default")
      (node (ref "JP4") (pin "1") (pinfunction "1_1") (pintype "passive"))
      (node (ref "TEMP49") (pin "DQ") (pinfunction "DQ_DQ") (pintype "bidirectional"))
      (node (ref "TEMP49") (pin "DQ1") (pinfunction "DQ_DQ1") (pintype "bidirectional"))
      (node (ref "TEMP49") (pin "DQ2") (pinfunction "DQ_DQ2") (pintype "bidirectional"))
    )
    (net (code "50") (name "D2") (class "Default")
      (node (ref "JP4") (pin "2") (pinfunction "2_2") (pintype "passive"))
      (node (ref "TEMP50") (pin "DQ") (pinfunction "DQ_DQ") (pintype "bidirectional"))
      (node (ref "TEMP50") (pin "DQ1") (pinfunction "DQ_DQ1") (pintype "bidirectional"))
      (node (ref "TEMP50") (pin "DQ2") (pinfunction "DQ_DQ2") (pintype "bidirectional"))
    )
    (net (code "51") (name "D3") (class "Default")
      (node (ref "JP4") (pin "3") (pinfunction "3_3") (pintype "passive"))
      (node (ref "TEMP51") (pin "DQ") (pinfunction "DQ_DQ") (pintype "bidirectional"))
      (node (ref "TEMP51") (pin "DQ1") (pinfunction "DQ_DQ1") (pintype "bidirectional"))
      (node (ref "TEMP51") (pin "DQ2") (pinfunction "DQ_DQ2") (pintype "bidirectional"))
    )
    (net (code "52") (name "D4") (class "Default")
      (node (ref "JP4") (pin "4") (pinfunction "4_4") (pintype "passive"))
      (node (ref "TEMP52") (pin "DQ") (pinfunction "DQ_DQ") (pintype "bidirectional"))
      (node (ref "TEMP52") (pin "DQ1") (pinfunction "DQ_DQ1") (pintype "bidirectional"))
      (node (ref "TEMP52") (pin "DQ2") (pinfunction "DQ_DQ2") (pintype "bidirectional"))
    )
    (net (code "53") (name "D5") (class "Default")
      (node (ref "JP4") (pin "5") (pinfunction "5_5") (pintype "passive"))
      (node (ref "TEMP53") (pin "DQ") (pinfunction "DQ_DQ") (pintype "bidirectional"))
      (node (ref "TEMP53") (pin "DQ1") (pinfunction "DQ_DQ1") (pintype "bidirectional"))
      (node (ref "TEMP53") (pin "DQ2") (pinfunction "DQ_DQ2") (pintype "bidirectional"))
    )
    (net (code "54") (name "D6") (class "Default")
      (node (ref "JP4") (pin "6") (pinfunction "6_6") (pintype "passive"))
      (node (ref "TEMP54") (pin "DQ") (pinfunction "DQ_DQ") (pintype "bidirectional"))
      (node (ref "TEMP54") (pin "DQ1") (pinfunction "DQ_DQ1") (pintype "bidirectional"))
      (node (ref "TEMP54") (pin "DQ2") (pinfunction "DQ_DQ2") (pintype "bidirectional"))
    )
    (net (code "55") (name "D7") (class "Default")
      (node (ref "JP4") (pin "7") (pinfunction "7_7") (pintype "passive"))
      (node (ref "TEMP55") (pin "DQ") (pinfunction "DQ_DQ") (pintype "bidirectional"))
      (node (ref "TEMP55") (pin "DQ1") (pinfunction "DQ_DQ1") (pintype "bidirectional"))
      (node (ref "TEMP55") (pin "DQ2") (pinfunction "DQ_DQ2") (pintype "bidirectional"))
    )
    (net (code "56") (name "D8") (class "Default")
      (node (ref "JP4") (pin "8") (pinfunction "8_8") (pintype "passive"))
      (node (ref "TEMP56") (pin "DQ") (pinfunction "DQ_DQ") (pintype "bidirectional"))
      (node (ref "TEMP56") (pin "DQ1") (pinfunction "DQ_DQ1") (pintype "bidirectional"))
      (node (ref "TEMP56") (pin "DQ2") (pinfunction "DQ_DQ2") (pintype "bidirectional"))
    )
    (net (code "57") (name "D9") (class "Default")
      (node (ref "JP4") (pin "9") (pinfunction "9_9") (pintype "passive"))
      (node (ref "TEMP57") (pin "DQ") (pinfunction "DQ_DQ") (pintype "bidirectional"))
      (node (ref "TEMP57") (pin "DQ1") (pinfunction "DQ_DQ1") (pintype "bidirectional"))
      (node (ref "TEMP57") (pin "DQ2") (pinfunction "DQ_DQ2") (pintype "bidirectional"))
    )
    (net (code "58") (name "D10") (class "Default")
      (node (ref "JP4") (pin "10") (pinfunction "10_10") (pintype "passive"))
      (node (ref "TEMP58") (pin "DQ") (pinfunction "DQ_DQ") (pintype "bidirectional"))
      (node (ref "TEMP58") (pin "DQ1") (pinfunction "DQ_DQ1") (pintype "bidirectional"))
      (node (ref "TEMP58") (pin "DQ2") (pinfunction "DQ_DQ2") (pintype "bidirectional"))
    )
    (net (code "59") (name "D11") (class "Default")
      (node (ref "JP4") (pin "11") (pinfunction "11_11") (pintype "passive"))
      (node (ref "TEMP59") (pin "DQ") (pinfunction "DQ_DQ") (pintype "bidirectional"))
      (node (ref "TEMP59") (pin "DQ1") (pinfunction "DQ_DQ1") (pintype "bidirectional"))
      (node (ref "TEMP59") (pin "DQ2") (pinfunction "DQ_DQ2") (pintype "bidirectional"))
    )
    (net (code "60") (name "D12") (class "Default")
      (node (ref "JP4") (pin "12") (pinfunction "12_12") (pintype "passive"))
      (node (ref "TEMP60") (pin "DQ") (pinfunction "DQ_DQ") (pintype "bidirectional"))
      (node (ref "TEMP60") (pin "DQ1") (pinfunction "DQ_DQ1") (pintype "bidirectional"))
      (node (ref "TEMP60") (pin "DQ2") (pinfunction "DQ_DQ2") (pintype "bidirectional"))
    )
    (net (code "61") (name "D13") (class "Default")
      (node (ref "JP4") (pin "13") (pinfunction "13_13") (pintype "passive"))
      (node (ref "TEMP61") (pin "DQ") (pinfunction "DQ_DQ") (pintype "bidirectional"))
      (node (ref "TEMP61") (pin "DQ1") (pinfunction "DQ_DQ1") (pintype "bidirectional"))
      (node (ref "TEMP61") (pin "DQ2") (pinfunction "DQ_DQ2") (pintype "bidirectional"))
    )
    (net (code "62") (name "D14") (class "Default")
      (node (ref "JP4") (pin "14") (pinfunction "14_14") (pintype "passive"))
      (node (ref "TEMP62") (pin "DQ") (pinfunction "DQ_DQ") (pintype "bidirectional"))
      (node (ref "TEMP62") (pin "DQ1") (pinfunction "DQ_DQ1") (pintype "bidirectional"))
      (node (ref "TEMP62") (pin "DQ2") (pinfunction "DQ_DQ2") (pintype "bidirectional"))
    )
    (net (code "63") (name "D15") (class "Default")
      (node (ref "JP4") (pin "15") (pinfunction "15_15") (pintype "passive"))
      (node (ref "TEMP63") (pin "DQ") (pinfunction "DQ_DQ") (pintype "bidirectional"))
      (node (ref "TEMP63") (pin "DQ1") (pinfunction "DQ_DQ1") (pintype "bidirectional"))
      (node (ref "TEMP63") (pin "DQ2") (pinfunction "DQ_DQ2") (pintype "bidirectional"))
    )
    (net (code "64") (name "D16") (class "Default")
      (node (ref "JP4") (pin "16") (pinfunction "16_16") (pintype "passive"))
      (node (ref "TEMP64") (pin "DQ") (pinfunction "DQ_DQ") (pintype "bidirectional"))
      (node (ref "TEMP64") (pin "DQ1") (pinfunction "DQ_DQ1") (pintype "bidirectional"))
      (node (ref "TEMP64") (pin "DQ2") (pinfunction "DQ_DQ2") (pintype "bidirectional"))
    )
    (net (code "65") (name "GND") (class "Default")
      (node (ref "J1") (pin "1") (pinfunction "1_1") (pintype "passive"))
      (node (ref "J1") (pin "2") (pinfunction "2_2") (pintype "passive"))
      (node (ref "J2") (pin "1") (pinfunction "1_1") (pintype "passive"))
      (node (ref "J2") (pin "2") (pinfunction "2_2") (pintype "passive"))
      (node (ref "J3") (pin "1") (pinfunction "1_1") (pintype "passive"))
      (node (ref "J3") (pin "2") (pinfunction "2_2") (pintype "passive"))
      (node (ref "J4") (pin "1") (pinfunction "1_1") (pintype "passive"))
      (node (ref "J4") (pin "2") (pinfunction "2_2") (pintype "passive"))
      (node (ref "TEMP1") (pin "GND") (pinfunction "GND_GND") (pintype "bidirectional"))
      (node (ref "TEMP1") (pin "GND1") (pinfunction "GND_GND1") (pintype "bidirectional"))
      (node (ref "TEMP1") (pin "GND2") (pinfunction "GND_GND2") (pintype "bidirectional"))
      (node (ref "TEMP1") (pin "VDD") (pinfunction "GND_VDD") (pintype "bidirectional"))
      (node (ref "TEMP10") (pin "GND") (pinfunction "GND_GND") (pintype "bidirectional"))
      (node (ref "TEMP10") (pin "GND1") (pinfunction "GND_GND1") (pintype "bidirectional"))
      (node (ref "TEMP10") (pin "GND2") (pinfunction "GND_GND2") (pintype "bidirectional"))
      (node (ref "TEMP10") (pin "VDD") (pinfunction "GND_VDD") (pintype "bidirectional"))
      (node (ref "TEMP11") (pin "GND") (pinfunction "GND_GND") (pintype "bidirectional"))
      (node (ref "TEMP11") (pin "GND1") (pinfunction "GND_GND1") (pintype "bidirectional"))
      (node (ref "TEMP11") (pin "GND2") (pinfunction "GND_GND2") (pintype "bidirectional"))
      (node (ref "TEMP11") (pin "VDD") (pinfunction "GND_VDD") (pintype "bidirectional"))
      (node (ref "TEMP12") (pin "GND") (pinfunction "GND_GND") (pintype "bidirectional"))
      (node (ref "TEMP12") (pin "GND1") (pinfunction "GND_GND1") (pintype "bidirectional"))
      (node (ref "TEMP12") (pin "GND2") (pinfunction "GND_GND2") (pintype "bidirectional"))
      (node (ref "TEMP12") (pin "VDD") (pinfunction "GND_VDD") (pintype "bidirectional"))
      (node (ref "TEMP13") (pin "GND") (pinfunction "GND_GND") (pintype "bidirectional"))
      (node (ref "TEMP13") (pin "GND1") (pinfunction "GND_GND1") (pintype "bidirectional"))
      (node (ref "TEMP13") (pin "GND2") (pinfunction "GND_GND2") (pintype "bidirectional"))
      (node (ref "TEMP13") (pin "VDD") (pinfunction "GND_VDD") (pintype "bidirectional"))
      (node (ref "TEMP14") (pin "GND") (pinfunction "GND_GND") (pintype "bidirectional"))
      (node (ref "TEMP14") (pin "GND1") (pinfunction "GND_GND1") (pintype "bidirectional"))
      (node (ref "TEMP14") (pin "GND2") (pinfunction "GND_GND2") (pintype "bidirectional"))
      (node (ref "TEMP14") (pin "VDD") (pinfunction "GND_VDD") (pintype "bidirectional"))
      (node (ref "TEMP15") (pin "GND") (pinfunction "GND_GND") (pintype "bidirectional"))
      (node (ref "TEMP15") (pin "GND1") (pinfunction "GND_GND1") (pintype "bidirectional"))
      (node (ref "TEMP15") (pin "GND2") (pinfunction "GND_GND2") (pintype "bidirectional"))
      (node (ref "TEMP15") (pin "VDD") (pinfunction "GND_VDD") (pintype "bidirectional"))
      (node (ref "TEMP16") (pin "GND") (pinfunction "GND_GND") (pintype "bidirectional"))
      (node (ref "TEMP16") (pin "GND1") (pinfunction "GND_GND1") (pintype "bidirectional"))
      (node (ref "TEMP16") (pin "GND2") (pinfunction "GND_GND2") (pintype "bidirectional"))
      (node (ref "TEMP16") (pin "VDD") (pinfunction "GND_VDD") (pintype "bidirectional"))
      (node (ref "TEMP17") (pin "GND") (pinfunction "GND_GND") (pintype "bidirectional"))
      (node (ref "TEMP17") (pin "GND1") (pinfunction "GND_GND1") (pintype "bidirectional"))
      (node (ref "TEMP17") (pin "GND2") (pinfunction "GND_GND2") (pintype "bidirectional"))
      (node (ref "TEMP17") (pin "VDD") (pinfunction "GND_VDD") (pintype "bidirectional"))
      (node (ref "TEMP18") (pin "GND") (pinfunction "GND_GND") (pintype "bidirectional"))
      (node (ref "TEMP18") (pin "GND1") (pinfunction "GND_GND1") (pintype "bidirectional"))
      (node (ref "TEMP18") (pin "GND2") (pinfunction "GND_GND2") (pintype "bidirectional"))
      (node (ref "TEMP18") (pin "VDD") (pinfunction "GND_VDD") (pintype "bidirectional"))
      (node (ref "TEMP19") (pin "GND") (pinfunction "GND_GND") (pintype "bidirectional"))
      (node (ref "TEMP19") (pin "GND1") (pinfunction "GND_GND1") (pintype "bidirectional"))
      (node (ref "TEMP19") (pin "GND2") (pinfunction "GND_GND2") (pintype "bidirectional"))
      (node (ref "TEMP19") (pin "VDD") (pinfunction "GND_VDD") (pintype "bidirectional"))
      (node (ref "TEMP2") (pin "GND") (pinfunction "GND_GND") (pintype "bidirectional"))
      (node (ref "TEMP2") (pin "GND1") (pinfunction "GND_GND1") (pintype "bidirectional"))
      (node (ref "TEMP2") (pin "GND2") (pinfunction "GND_GND2") (pintype "bidirectional"))
      (node (ref "TEMP2") (pin "VDD") (pinfunction "GND_VDD") (pintype "bidirectional"))
      (node (ref "TEMP20") (pin "GND") (pinfunction "GND_GND") (pintype "bidirectional"))
      (node (ref "TEMP20") (pin "GND1") (pinfunction "GND_GND1") (pintype "bidirectional"))
      (node (ref "TEMP20") (pin "GND2") (pinfunction "GND_GND2") (pintype "bidirectional"))
      (node (ref "TEMP20") (pin "VDD") (pinfunction "GND_VDD") (pintype "bidirectional"))
      (node (ref "TEMP21") (pin "GND") (pinfunction "GND_GND") (pintype "bidirectional"))
      (node (ref "TEMP21") (pin "GND1") (pinfunction "GND_GND1") (pintype "bidirectional"))
      (node (ref "TEMP21") (pin "GND2") (pinfunction "GND_GND2") (pintype "bidirectional"))
      (node (ref "TEMP21") (pin "VDD") (pinfunction "GND_VDD") (pintype "bidirectional"))
      (node (ref "TEMP22") (pin "GND") (pinfunction "GND_GND") (pintype "bidirectional"))
      (node (ref "TEMP22") (pin "GND1") (pinfunction "GND_GND1") (pintype "bidirectional"))
      (node (ref "TEMP22") (pin "GND2") (pinfunction "GND_GND2") (pintype "bidirectional"))
      (node (ref "TEMP22") (pin "VDD") (pinfunction "GND_VDD") (pintype "bidirectional"))
      (node (ref "TEMP23") (pin "GND") (pinfunction "GND_GND") (pintype "bidirectional"))
      (node (ref "TEMP23") (pin "GND1") (pinfunction "GND_GND1") (pintype "bidirectional"))
      (node (ref "TEMP23") (pin "GND2") (pinfunction "GND_GND2") (pintype "bidirectional"))
      (node (ref "TEMP23") (pin "VDD") (pinfunction "GND_VDD") (pintype "bidirectional"))
      (node (ref "TEMP24") (pin "GND") (pinfunction "GND_GND") (pintype "bidirectional"))
      (node (ref "TEMP24") (pin "GND1") (pinfunction "GND_GND1") (pintype "bidirectional"))
      (node (ref "TEMP24") (pin "GND2") (pinfunction "GND_GND2") (pintype "bidirectional"))
      (node (ref "TEMP24") (pin "VDD") (pinfunction "GND_VDD") (pintype "bidirectional"))
      (node (ref "TEMP25") (pin "GND") (pinfunction "GND_GND") (pintype "bidirectional"))
      (node (ref "TEMP25") (pin "GND1") (pinfunction "GND_GND1") (pintype "bidirectional"))
      (node (ref "TEMP25") (pin "GND2") (pinfunction "GND_GND2") (pintype "bidirectional"))
      (node (ref "TEMP25") (pin "VDD") (pinfunction "GND_VDD") (pintype "bidirectional"))
      (node (ref "TEMP26") (pin "GND") (pinfunction "GND_GND") (pintype "bidirectional"))
      (node (ref "TEMP26") (pin "GND1") (pinfunction "GND_GND1") (pintype "bidirectional"))
      (node (ref "TEMP26") (pin "GND2") (pinfunction "GND_GND2") (pintype "bidirectional"))
      (node (ref "TEMP26") (pin "VDD") (pinfunction "GND_VDD") (pintype "bidirectional"))
      (node (ref "TEMP27") (pin "GND") (pinfunction "GND_GND") (pintype "bidirectional"))
      (node (ref "TEMP27") (pin "GND1") (pinfunction "GND_GND1") (pintype "bidirectional"))
      (node (ref "TEMP27") (pin "GND2") (pinfunction "GND_GND2") (pintype "bidirectional"))
      (node (ref "TEMP27") (pin "VDD") (pinfunction "GND_VDD") (pintype "bidirectional"))
      (node (ref "TEMP28") (pin "GND") (pinfunction "GND_GND") (pintype "bidirectional"))
      (node (ref "TEMP28") (pin "GND1") (pinfunction "GND_GND1") (pintype "bidirectional"))
      (node (ref "TEMP28") (pin "GND2") (pinfunction "GND_GND2") (pintype "bidirectional"))
      (node (ref "TEMP28") (pin "VDD") (pinfunction "GND_VDD") (pintype "bidirectional"))
      (node (ref "TEMP29") (pin "GND") (pinfunction "GND_GND") (pintype "bidirectional"))
      (node (ref "TEMP29") (pin "GND1") (pinfunction "GND_GND1") (pintype "bidirectional"))
      (node (ref "TEMP29") (pin "GND2") (pinfunction "GND_GND2") (pintype "bidirectional"))
      (node (ref "TEMP29") (pin "VDD") (pinfunction "GND_VDD") (pintype "bidirectional"))
      (node (ref "TEMP3") (pin "GND") (pinfunction "GND_GND") (pintype "bidirectional"))
      (node (ref "TEMP3") (pin "GND1") (pinfunction "GND_GND1") (pintype "bidirectional"))
      (node (ref "TEMP3") (pin "GND2") (pinfunction "GND_GND2") (pintype "bidirectional"))
      (node (ref "TEMP3") (pin "VDD") (pinfunction "GND_VDD") (pintype "bidirectional"))
      (node (ref "TEMP30") (pin "GND") (pinfunction "GND_GND") (pintype "bidirectional"))
      (node (ref "TEMP30") (pin "GND1") (pinfunction "GND_GND1") (pintype "bidirectional"))
      (node (ref "TEMP30") (pin "GND2") (pinfunction "GND_GND2") (pintype "bidirectional"))
      (node (ref "TEMP30") (pin "VDD") (pinfunction "GND_VDD") (pintype "bidirectional"))
      (node (ref "TEMP31") (pin "GND") (pinfunction "GND_GND") (pintype "bidirectional"))
      (node (ref "TEMP31") (pin "GND1") (pinfunction "GND_GND1") (pintype "bidirectional"))
      (node (ref "TEMP31") (pin "GND2") (pinfunction "GND_GND2") (pintype "bidirectional"))
      (node (ref "TEMP31") (pin "VDD") (pinfunction "GND_VDD") (pintype "bidirectional"))
      (node (ref "TEMP32") (pin "GND") (pinfunction "GND_GND") (pintype "bidirectional"))
      (node (ref "TEMP32") (pin "GND1") (pinfunction "GND_GND1") (pintype "bidirectional"))
      (node (ref "TEMP32") (pin "GND2") (pinfunction "GND_GND2") (pintype "bidirectional"))
      (node (ref "TEMP32") (pin "VDD") (pinfunction "GND_VDD") (pintype "bidirectional"))
      (node (ref "TEMP33") (pin "GND") (pinfunction "GND_GND") (pintype "bidirectional"))
      (node (ref "TEMP33") (pin "GND1") (pinfunction "GND_GND1") (pintype "bidirectional"))
      (node (ref "TEMP33") (pin "GND2") (pinfunction "GND_GND2") (pintype "bidirectional"))
      (node (ref "TEMP33") (pin "VDD") (pinfunction "GND_VDD") (pintype "bidirectional"))
      (node (ref "TEMP34") (pin "GND") (pinfunction "GND_GND") (pintype "bidirectional"))
      (node (ref "TEMP34") (pin "GND1") (pinfunction "GND_GND1") (pintype "bidirectional"))
      (node (ref "TEMP34") (pin "GND2") (pinfunction "GND_GND2") (pintype "bidirectional"))
      (node (ref "TEMP34") (pin "VDD") (pinfunction "GND_VDD") (pintype "bidirectional"))
      (node (ref "TEMP35") (pin "GND") (pinfunction "GND_GND") (pintype "bidirectional"))
      (node (ref "TEMP35") (pin "GND1") (pinfunction "GND_GND1") (pintype "bidirectional"))
      (node (ref "TEMP35") (pin "GND2") (pinfunction "GND_GND2") (pintype "bidirectional"))
      (node (ref "TEMP35") (pin "VDD") (pinfunction "GND_VDD") (pintype "bidirectional"))
      (node (ref "TEMP36") (pin "GND") (pinfunction "GND_GND") (pintype "bidirectional"))
      (node (ref "TEMP36") (pin "GND1") (pinfunction "GND_GND1") (pintype "bidirectional"))
      (node (ref "TEMP36") (pin "GND2") (pinfunction "GND_GND2") (pintype "bidirectional"))
      (node (ref "TEMP36") (pin "VDD") (pinfunction "GND_VDD") (pintype "bidirectional"))
      (node (ref "TEMP37") (pin "GND") (pinfunction "GND_GND") (pintype "bidirectional"))
      (node (ref "TEMP37") (pin "GND1") (pinfunction "GND_GND1") (pintype "bidirectional"))
      (node (ref "TEMP37") (pin "GND2") (pinfunction "GND_GND2") (pintype "bidirectional"))
      (node (ref "TEMP37") (pin "VDD") (pinfunction "GND_VDD") (pintype "bidirectional"))
      (node (ref "TEMP38") (pin "GND") (pinfunction "GND_GND") (pintype "bidirectional"))
      (node (ref "TEMP38") (pin "GND1") (pinfunction "GND_GND1") (pintype "bidirectional"))
      (node (ref "TEMP38") (pin "GND2") (pinfunction "GND_GND2") (pintype "bidirectional"))
      (node (ref "TEMP38") (pin "VDD") (pinfunction "GND_VDD") (pintype "bidirectional"))
      (node (ref "TEMP39") (pin "GND") (pinfunction "GND_GND") (pintype "bidirectional"))
      (node (ref "TEMP39") (pin "GND1") (pinfunction "GND_GND1") (pintype "bidirectional"))
      (node (ref "TEMP39") (pin "GND2") (pinfunction "GND_GND2") (pintype "bidirectional"))
      (node (ref "TEMP39") (pin "VDD") (pinfunction "GND_VDD") (pintype "bidirectional"))
      (node (ref "TEMP4") (pin "GND") (pinfunction "GND_GND") (pintype "bidirectional"))
      (node (ref "TEMP4") (pin "GND1") (pinfunction "GND_GND1") (pintype "bidirectional"))
      (node (ref "TEMP4") (pin "GND2") (pinfunction "GND_GND2") (pintype "bidirectional"))
      (node (ref "TEMP4") (pin "VDD") (pinfunction "GND_VDD") (pintype "bidirectional"))
      (node (ref "TEMP40") (pin "GND") (pinfunction "GND_GND") (pintype "bidirectional"))
      (node (ref "TEMP40") (pin "GND1") (pinfunction "GND_GND1") (pintype "bidirectional"))
      (node (ref "TEMP40") (pin "GND2") (pinfunction "GND_GND2") (pintype "bidirectional"))
      (node (ref "TEMP40") (pin "VDD") (pinfunction "GND_VDD") (pintype "bidirectional"))
      (node (ref "TEMP41") (pin "GND") (pinfunction "GND_GND") (pintype "bidirectional"))
      (node (ref "TEMP41") (pin "GND1") (pinfunction "GND_GND1") (pintype "bidirectional"))
      (node (ref "TEMP41") (pin "GND2") (pinfunction "GND_GND2") (pintype "bidirectional"))
      (node (ref "TEMP41") (pin "VDD") (pinfunction "GND_VDD") (pintype "bidirectional"))
      (node (ref "TEMP42") (pin "GND") (pinfunction "GND_GND") (pintype "bidirectional"))
      (node (ref "TEMP42") (pin "GND1") (pinfunction "GND_GND1") (pintype "bidirectional"))
      (node (ref "TEMP42") (pin "GND2") (pinfunction "GND_GND2") (pintype "bidirectional"))
      (node (ref "TEMP42") (pin "VDD") (pinfunction "GND_VDD") (pintype "bidirectional"))
      (node (ref "TEMP43") (pin "GND") (pinfunction "GND_GND") (pintype "bidirectional"))
      (node (ref "TEMP43") (pin "GND1") (pinfunction "GND_GND1") (pintype "bidirectional"))
      (node (ref "TEMP43") (pin "GND2") (pinfunction "GND_GND2") (pintype "bidirectional"))
      (node (ref "TEMP43") (pin "VDD") (pinfunction "GND_VDD") (pintype "bidirectional"))
      (node (ref "TEMP44") (pin "GND") (pinfunction "GND_GND") (pintype "bidirectional"))
      (node (ref "TEMP44") (pin "GND1") (pinfunction "GND_GND1") (pintype "bidirectional"))
      (node (ref "TEMP44") (pin "GND2") (pinfunction "GND_GND2") (pintype "bidirectional"))
      (node (ref "TEMP44") (pin "VDD") (pinfunction "GND_VDD") (pintype "bidirectional"))
      (node (ref "TEMP45") (pin "GND") (pinfunction "GND_GND") (pintype "bidirectional"))
      (node (ref "TEMP45") (pin "GND1") (pinfunction "GND_GND1") (pintype "bidirectional"))
      (node (ref "TEMP45") (pin "GND2") (pinfunction "GND_GND2") (pintype "bidirectional"))
      (node (ref "TEMP45") (pin "VDD") (pinfunction "GND_VDD") (pintype "bidirectional"))
      (node (ref "TEMP46") (pin "GND") (pinfunction "GND_GND") (pintype "bidirectional"))
      (node (ref "TEMP46") (pin "GND1") (pinfunction "GND_GND1") (pintype "bidirectional"))
      (node (ref "TEMP46") (pin "GND2") (pinfunction "GND_GND2") (pintype "bidirectional"))
      (node (ref "TEMP46") (pin "VDD") (pinfunction "GND_VDD") (pintype "bidirectional"))
      (node (ref "TEMP47") (pin "GND") (pinfunction "GND_GND") (pintype "bidirectional"))
      (node (ref "TEMP47") (pin "GND1") (pinfunction "GND_GND1") (pintype "bidirectional"))
      (node (ref "TEMP47") (pin "GND2") (pinfunction "GND_GND2") (pintype "bidirectional"))
      (node (ref "TEMP47") (pin "VDD") (pinfunction "GND_VDD") (pintype "bidirectional"))
      (node (ref "TEMP48") (pin "GND") (pinfunction "GND_GND") (pintype "bidirectional"))
      (node (ref "TEMP48") (pin "GND1") (pinfunction "GND_GND1") (pintype "bidirectional"))
      (node (ref "TEMP48") (pin "GND2") (pinfunction "GND_GND2") (pintype "bidirectional"))
      (node (ref "TEMP48") (pin "VDD") (pinfunction "GND_VDD") (pintype "bidirectional"))
      (node (ref "TEMP49") (pin "GND") (pinfunction "GND_GND") (pintype "bidirectional"))
      (node (ref "TEMP49") (pin "GND1") (pinfunction "GND_GND1") (pintype "bidirectional"))
      (node (ref "TEMP49") (pin "GND2") (pinfunction "GND_GND2") (pintype "bidirectional"))
      (node (ref "TEMP49") (pin "VDD") (pinfunction "GND_VDD") (pintype "bidirectional"))
      (node (ref "TEMP5") (pin "GND") (pinfunction "GND_GND") (pintype "bidirectional"))
      (node (ref "TEMP5") (pin "GND1") (pinfunction "GND_GND1") (pintype "bidirectional"))
      (node (ref "TEMP5") (pin "GND2") (pinfunction "GND_GND2") (pintype "bidirectional"))
      (node (ref "TEMP5") (pin "VDD") (pinfunction "GND_VDD") (pintype "bidirectional"))
      (node (ref "TEMP50") (pin "GND") (pinfunction "GND_GND") (pintype "bidirectional"))
      (node (ref "TEMP50") (pin "GND1") (pinfunction "GND_GND1") (pintype "bidirectional"))
      (node (ref "TEMP50") (pin "GND2") (pinfunction "GND_GND2") (pintype "bidirectional"))
      (node (ref "TEMP50") (pin "VDD") (pinfunction "GND_VDD") (pintype "bidirectional"))
      (node (ref "TEMP51") (pin "GND") (pinfunction "GND_GND") (pintype "bidirectional"))
      (node (ref "TEMP51") (pin "GND1") (pinfunction "GND_GND1") (pintype "bidirectional"))
      (node (ref "TEMP51") (pin "GND2") (pinfunction "GND_GND2") (pintype "bidirectional"))
      (node (ref "TEMP51") (pin "VDD") (pinfunction "GND_VDD") (pintype "bidirectional"))
      (node (ref "TEMP52") (pin "GND") (pinfunction "GND_GND") (pintype "bidirectional"))
      (node (ref "TEMP52") (pin "GND1") (pinfunction "GND_GND1") (pintype "bidirectional"))
      (node (ref "TEMP52") (pin "GND2") (pinfunction "GND_GND2") (pintype "bidirectional"))
      (node (ref "TEMP52") (pin "VDD") (pinfunction "GND_VDD") (pintype "bidirectional"))
      (node (ref "TEMP53") (pin "GND") (pinfunction "GND_GND") (pintype "bidirectional"))
      (node (ref "TEMP53") (pin "GND1") (pinfunction "GND_GND1") (pintype "bidirectional"))
      (node (ref "TEMP53") (pin "GND2") (pinfunction "GND_GND2") (pintype "bidirectional"))
      (node (ref "TEMP53") (pin "VDD") (pinfunction "GND_VDD") (pintype "bidirectional"))
      (node (ref "TEMP54") (pin "GND") (pinfunction "GND_GND") (pintype "bidirectional"))
      (node (ref "TEMP54") (pin "GND1") (pinfunction "GND_GND1") (pintype "bidirectional"))
      (node (ref "TEMP54") (pin "GND2") (pinfunction "GND_GND2") (pintype "bidirectional"))
      (node (ref "TEMP54") (pin "VDD") (pinfunction "GND_VDD") (pintype "bidirectional"))
      (node (ref "TEMP55") (pin "GND") (pinfunction "GND_GND") (pintype "bidirectional"))
      (node (ref "TEMP55") (pin "GND1") (pinfunction "GND_GND1") (pintype "bidirectional"))
      (node (ref "TEMP55") (pin "GND2") (pinfunction "GND_GND2") (pintype "bidirectional"))
      (node (ref "TEMP55") (pin "VDD") (pinfunction "GND_VDD") (pintype "bidirectional"))
      (node (ref "TEMP56") (pin "GND") (pinfunction "GND_GND") (pintype "bidirectional"))
      (node (ref "TEMP56") (pin "GND1") (pinfunction "GND_GND1") (pintype "bidirectional"))
      (node (ref "TEMP56") (pin "GND2") (pinfunction "GND_GND2") (pintype "bidirectional"))
      (node (ref "TEMP56") (pin "VDD") (pinfunction "GND_VDD") (pintype "bidirectional"))
      (node (ref "TEMP57") (pin "GND") (pinfunction "GND_GND") (pintype "bidirectional"))
      (node (ref "TEMP57") (pin "GND1") (pinfunction "GND_GND1") (pintype "bidirectional"))
      (node (ref "TEMP57") (pin "GND2") (pinfunction "GND_GND2") (pintype "bidirectional"))
      (node (ref "TEMP57") (pin "VDD") (pinfunction "GND_VDD") (pintype "bidirectional"))
      (node (ref "TEMP58") (pin "GND") (pinfunction "GND_GND") (pintype "bidirectional"))
      (node (ref "TEMP58") (pin "GND1") (pinfunction "GND_GND1") (pintype "bidirectional"))
      (node (ref "TEMP58") (pin "GND2") (pinfunction "GND_GND2") (pintype "bidirectional"))
      (node (ref "TEMP58") (pin "VDD") (pinfunction "GND_VDD") (pintype "bidirectional"))
      (node (ref "TEMP59") (pin "GND") (pinfunction "GND_GND") (pintype "bidirectional"))
      (node (ref "TEMP59") (pin "GND1") (pinfunction "GND_GND1") (pintype "bidirectional"))
      (node (ref "TEMP59") (pin "GND2") (pinfunction "GND_GND2") (pintype "bidirectional"))
      (node (ref "TEMP59") (pin "VDD") (pinfunction "GND_VDD") (pintype "bidirectional"))
      (node (ref "TEMP6") (pin "GND") (pinfunction "GND_GND") (pintype "bidirectional"))
      (node (ref "TEMP6") (pin "GND1") (pinfunction "GND_GND1") (pintype "bidirectional"))
      (node (ref "TEMP6") (pin "GND2") (pinfunction "GND_GND2") (pintype "bidirectional"))
      (node (ref "TEMP6") (pin "VDD") (pinfunction "GND_VDD") (pintype "bidirectional"))
      (node (ref "TEMP60") (pin "GND") (pinfunction "GND_GND") (pintype "bidirectional"))
      (node (ref "TEMP60") (pin "GND1") (pinfunction "GND_GND1") (pintype "bidirectional"))
      (node (ref "TEMP60") (pin "GND2") (pinfunction "GND_GND2") (pintype "bidirectional"))
      (node (ref "TEMP60") (pin "VDD") (pinfunction "GND_VDD") (pintype "bidirectional"))
      (node (ref "TEMP61") (pin "GND") (pinfunction "GND_GND") (pintype "bidirectional"))
      (node (ref "TEMP61") (pin "GND1") (pinfunction "GND_GND1") (pintype "bidirectional"))
      (node (ref "TEMP61") (pin "GND2") (pinfunction "GND_GND2") (pintype "bidirectional"))
      (node (ref "TEMP61") (pin "VDD") (pinfunction "GND_VDD") (pintype "bidirectional"))
      (node (ref "TEMP62") (pin "GND") (pinfunction "GND_GND") (pintype "bidirectional"))
      (node (ref "TEMP62") (pin "GND1") (pinfunction "GND_GND1") (pintype "bidirectional"))
      (node (ref "TEMP62") (pin "GND2") (pinfunction "GND_GND2") (pintype "bidirectional"))
      (node (ref "TEMP62") (pin "VDD") (pinfunction "GND_VDD") (pintype "bidirectional"))
      (node (ref "TEMP63") (pin "GND") (pinfunction "GND_GND") (pintype "bidirectional"))
      (node (ref "TEMP63") (pin "GND1") (pinfunction "GND_GND1") (pintype "bidirectional"))
      (node (ref "TEMP63") (pin "GND2") (pinfunction "GND_GND2") (pintype "bidirectional"))
      (node (ref "TEMP63") (pin "VDD") (pinfunction "GND_VDD") (pintype "bidirectional"))
      (node (ref "TEMP64") (pin "GND") (pinfunction "GND_GND") (pintype "bidirectional"))
      (node (ref "TEMP64") (pin "GND1") (pinfunction "GND_GND1") (pintype "bidirectional"))
      (node (ref "TEMP64") (pin "GND2") (pinfunction "GND_GND2") (pintype "bidirectional"))
      (node (ref "TEMP64") (pin "VDD") (pinfunction "GND_VDD") (pintype "bidirectional"))
      (node (ref "TEMP7") (pin "GND") (pinfunction "GND_GND") (pintype "bidirectional"))
      (node (ref "TEMP7") (pin "GND1") (pinfunction "GND_GND1") (pintype "bidirectional"))
      (node (ref "TEMP7") (pin "GND2") (pinfunction "GND_GND2") (pintype "bidirectional"))
      (node (ref "TEMP7") (pin "VDD") (pinfunction "GND_VDD") (pintype "bidirectional"))
      (node (ref "TEMP8") (pin "GND") (pinfunction "GND_GND") (pintype "bidirectional"))
      (node (ref "TEMP8") (pin "GND1") (pinfunction "GND_GND1") (pintype "bidirectional"))
      (node (ref "TEMP8") (pin "GND2") (pinfunction "GND_GND2") (pintype "bidirectional"))
      (node (ref "TEMP8") (pin "VDD") (pinfunction "GND_VDD") (pintype "bidirectional"))
      (node (ref "TEMP9") (pin "GND") (pinfunction "GND_GND") (pintype "bidirectional"))
      (node (ref "TEMP9") (pin "GND1") (pinfunction "GND_GND1") (pintype "bidirectional"))
      (node (ref "TEMP9") (pin "GND2") (pinfunction "GND_GND2") (pintype "bidirectional"))
      (node (ref "TEMP9") (pin "VDD") (pinfunction "GND_VDD") (pintype "bidirectional"))
    )
  )
)
